# LIS2DH_16g.net
KiCad netlist of a schematic drawn in EAGLE
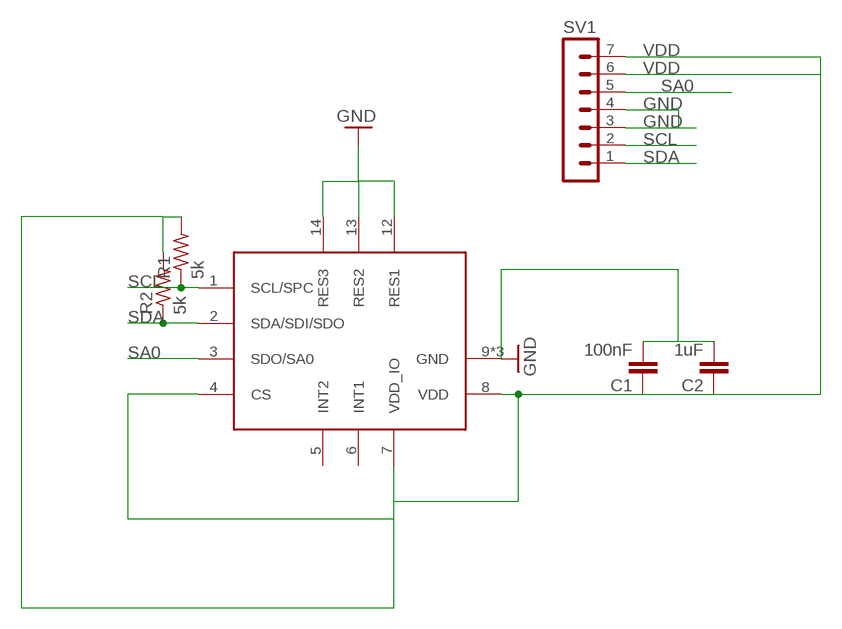
[diagram p0: schematic, sheet 1]

(export (version "E")
  (design (tool "Eeschema 10.0.6"))
  (components
    (comp (ref "C1")
      (value "100nF")
      (footprint "eagle-import:C0402")
      (libsource (lib "eagle-import") (part "C-EUC0402"))
    )
    (comp (ref "C2")
      (value "1uF")
      (footprint "eagle-import:C0402")
      (libsource (lib "eagle-import") (part "C-EUC0402"))
    )
    (comp (ref "R1")
      (value "5k")
      (footprint "eagle-import:R0402")
      (libsource (lib "eagle-import") (part "R-US_R0402"))
    )
    (comp (ref "R2")
      (value "5k")
      (footprint "eagle-import:R0402")
      (libsource (lib "eagle-import") (part "R-US_R0402"))
    )
    (comp (ref "SV1")
      (value "MA07-1")
      (footprint "eagle-import:MA07-1")
      (libsource (lib "eagle-import") (part "MA07-1"))
    )
    (comp (ref "U$1")
      (value "LISDH_16G")
      (footprint "eagle-import:LGA14_2X2")
      (libsource (lib "eagle-import") (part "LISDH_16G"))
    )
  )
  (nets
    (net (code "1") (name "/SA0") (class "Default")
      (node (ref "SV1") (pin "5") (pinfunction "5_5") (pintype "passive"))
      (node (ref "U$1") (pin "3") (pinfunction "SDO/SA0_3") (pintype "bidirectional"))
    )
    (net (code "2") (name "/SCL") (class "Default")
      (node (ref "R1") (pin "1") (pinfunction "1_1") (pintype "passive"))
      (node (ref "SV1") (pin "2") (pinfunction "2_2") (pintype "passive"))
      (node (ref "U$1") (pin "1") (pinfunction "SCL/SPC_1") (pintype "bidirectional"))
    )
    (net (code "3") (name "/SDA") (class "Default")
      (node (ref "R2") (pin "1") (pinfunction "1_1") (pintype "passive"))
      (node (ref "SV1") (pin "1") (pinfunction "1_1") (pintype "passive"))
      (node (ref "U$1") (pin "2") (pinfunction "SDA/SDI/SDO_2") (pintype "bidirectional"))
    )
    (net (code "4") (name "/VDD") (class "Default")
      (node (ref "C1") (pin "1") (pinfunction "1_1") (pintype "passive"))
      (node (ref "C2") (pin "1") (pinfunction "1_1") (pintype "passive"))
      (node (ref "R1") (pin "2") (pinfunction "2_2") (pintype "passive"))
      (node (ref "R2") (pin "2") (pinfunction "2_2") (pintype "passive"))
      (node (ref "SV1") (pin "6") (pinfunction "6_6") (pintype "passive"))
      (node (ref "SV1") (pin "7") (pinfunction "7_7") (pintype "passive"))
      (node (ref "U$1") (pin "4") (pinfunction "CS_4") (pintype "bidirectional"))
      (node (ref "U$1") (pin "7") (pinfunction "VDD_IO_7") (pintype "bidirectional"))
      (node (ref "U$1") (pin "8") (pinfunction "VDD_8") (pintype "bidirectional"))
    )
    (net (code "5") (name "GND") (class "Default")
      (node (ref "C1") (pin "2") (pinfunction "2_2") (pintype "passive"))
      (node (ref "C2") (pin "2") (pinfunction "2_2") (pintype "passive"))
      (node (ref "SV1") (pin "3") (pinfunction "3_3") (pintype "passive"))
      (node (ref "SV1") (pin "4") (pinfunction "4_4") (pintype "passive"))
      (node (ref "U$1") (pin "10") (pinfunction "GND_10") (pintype "bidirectional"))
      (node (ref "U$1") (pin "11") (pinfunction "GND_11") (pintype "bidirectional"))
      (node (ref "U$1") (pin "12") (pinfunction "RES1_12") (pintype "bidirectional"))
      (node (ref "U$1") (pin "13") (pinfunction "RES2_13") (pintype "bidirectional"))
      (node (ref "U$1") (pin "14") (pinfunction "RES3_14") (pintype "bidirectional"))
      (node (ref "U$1") (pin "9") (pinfunction "GND_9") (pintype "bidirectional"))
    )
    (net (code "6") (name "unconnected-(U$1-INT1-Pad6)") (class "Default")
      (node (ref "U$1") (pin "6") (pinfunction "INT1_6") (pintype "bidirectional"))
    )
    (net (code "7") (name "unconnected-(U$1-INT2-Pad5)") (class "Default")
      (node (ref "U$1") (pin "5") (pinfunction "INT2_5") (pintype "bidirectional"))
    )
  )
)
